# solarSwitcherV2_0.net
KiCad netlist of a schematic drawn in EAGLE
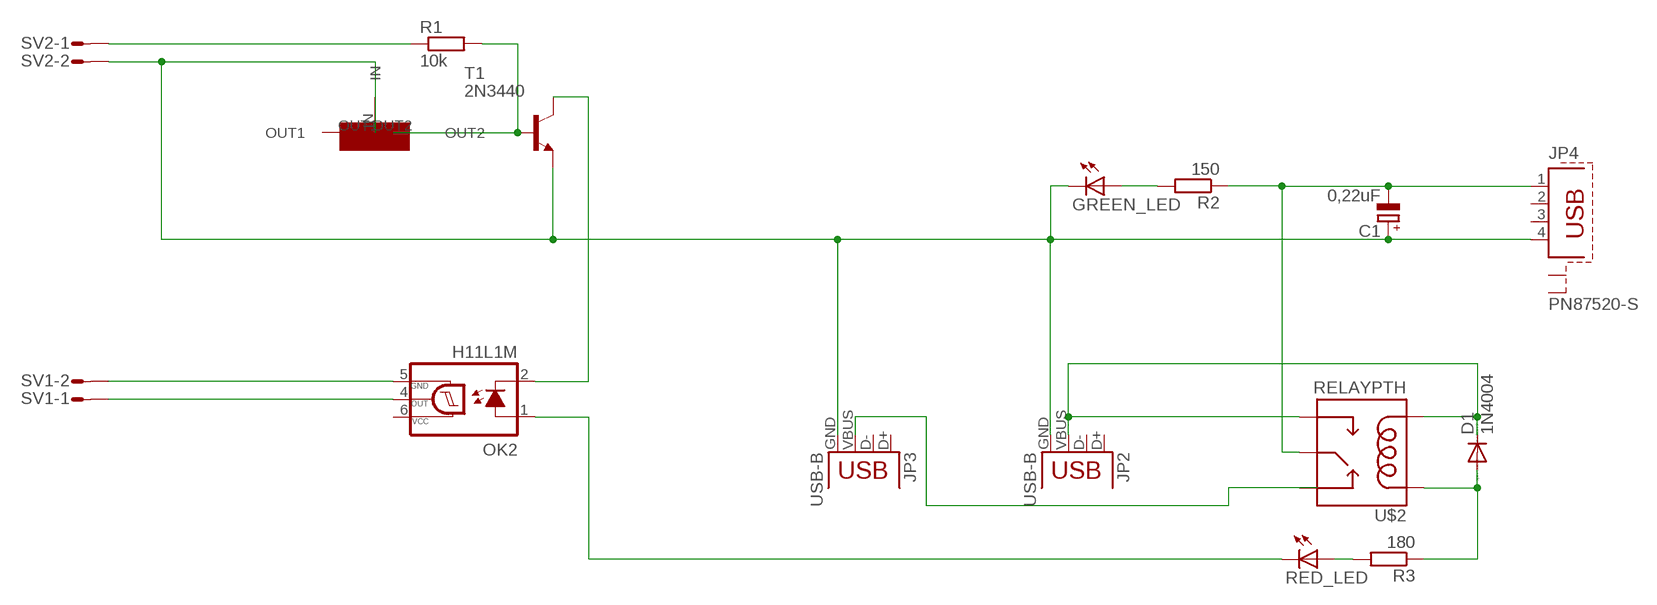
[diagram p0: schematic, sheet 1]

(export (version "E")
  (design (tool "Eeschema 10.0.6"))
  (components
    (comp (ref "C1")
      (value "0,22uF")
      (footprint "eagle-import:150CLZ-1014")
      (libsource (lib "eagle-import") (part "CPOL-EU150CLZ-1014"))
    )
    (comp (ref "D1")
      (value "1N4004")
      (footprint "eagle-import:DO41-10")
      (libsource (lib "eagle-import") (part "1N4004"))
    )
    (comp (ref "GREEN_LED")
      (value "LED5MM")
      (footprint "eagle-import:LED5MM")
      (libsource (lib "eagle-import") (part "LED5MM"))
    )
    (comp (ref "JP2")
      (value "USB-B")
      (footprint "eagle-import:USB-B-PTH")
      (libsource (lib "eagle-import") (part "USBPTH"))
    )
    (comp (ref "JP3")
      (value "USB-B")
      (footprint "eagle-import:USB-B-PTH")
      (libsource (lib "eagle-import") (part "USBPTH"))
    )
    (comp (ref "JP4")
      (value "PN87520-S")
      (footprint "eagle-import:PN87520-S")
      (libsource (lib "eagle-import") (part "PN87520-S"))
    )
    (comp (ref "OK2")
      (value "H11L1M")
      (footprint "eagle-import:DIL06")
      (fields (field (name "MF") "FAIRCHILD SEMICONDUCTOR") (field (name "MPN") "H11L1-M"))
      (libsource (lib "eagle-import") (part "H11LM1"))
    )
    (comp (ref "R1")
      (value "10k")
      (footprint "eagle-import:0207_10")
      (libsource (lib "eagle-import") (part "R-EU_0207/10"))
    )
    (comp (ref "R2")
      (value "150")
      (footprint "eagle-import:0207_10")
      (libsource (lib "eagle-import") (part "R-EU_0207/10"))
    )
    (comp (ref "R3")
      (value "180")
      (footprint "eagle-import:0207_10")
      (libsource (lib "eagle-import") (part "R-EU_0207/10"))
    )
    (comp (ref "RED_LED")
      (value "LED5MM")
      (footprint "eagle-import:LED5MM")
      (libsource (lib "eagle-import") (part "LED5MM"))
    )
    (comp (ref "SV1")
      (value "L02P")
      (footprint "eagle-import:L02P")
      (libsource (lib "eagle-import") (part "L02P"))
    )
    (comp (ref "SV2")
      (value "L02P")
      (footprint "eagle-import:L02P")
      (libsource (lib "eagle-import") (part "L02P"))
    )
    (comp (ref "T1")
      (value "2N3440")
      (footprint "eagle-import:TO5")
      (libsource (lib "eagle-import") (part "2N3440"))
    )
    (comp (ref "U$2")
      (value "RELAYPTH")
      (footprint "eagle-import:SRD-05VDC-SL-C")
      (libsource (lib "eagle-import") (part "RELAYPTH"))
    )
    (comp (ref "U$5")
      (value "20k")
      (footprint "eagle-import:POT_TRIMMER")
      (libsource (lib "eagle-import") (part "POT_TRIMMER"))
    )
  )
  (nets
    (net (code "1") (name "/VCC") (class "Default")
      (node (ref "OK2") (pin "6") (pinfunction "VCC_6") (pintype "power_in"))
    )
    (net (code "2") (name "Net-(C1-Pad-)") (class "Default")
      (node (ref "C1") (pin "-") (pinfunction "-_-") (pintype "passive"))
      (node (ref "JP4") (pin "1") (pinfunction "1_1") (pintype "passive"))
      (node (ref "R2") (pin "1") (pinfunction "1_1") (pintype "passive"))
      (node (ref "U$2") (pin "SWCOMMON") (pinfunction "SWCOMMON_SWCOMMON") (pintype "bidirectional"))
    )
    (net (code "3") (name "Net-(D1-PadA)") (class "Default")
      (node (ref "D1") (pin "A") (pinfunction "A_A") (pintype "passive"))
      (node (ref "R3") (pin "1") (pinfunction "1_1") (pintype "passive"))
      (node (ref "U$2") (pin "COIL1") (pinfunction "COIL1_COIL1") (pintype "bidirectional"))
    )
    (net (code "4") (name "Net-(D1-PadC)") (class "Default")
      (node (ref "D1") (pin "C") (pinfunction "C_C") (pintype "passive"))
      (node (ref "JP2") (pin "VBUS") (pinfunction "VBUS_VBUS") (pintype "bidirectional"))
      (node (ref "U$2") (pin "COIL0") (pinfunction "COIL0_COIL0") (pintype "bidirectional"))
      (node (ref "U$2") (pin "SWOPEN") (pinfunction "SWOPEN_SWOPEN") (pintype "bidirectional"))
    )
    (net (code "5") (name "Net-(GREEN_LED-C)") (class "Default")
      (node (ref "C1") (pin "+") (pinfunction "+_+") (pintype "passive"))
      (node (ref "GREEN_LED") (pin "K") (pinfunction "C_K") (pintype "passive"))
      (node (ref "JP2") (pin "GND") (pinfunction "GND_GND") (pintype "bidirectional"))
      (node (ref "JP3") (pin "GND") (pinfunction "GND_GND") (pintype "bidirectional"))
      (node (ref "JP4") (pin "4") (pinfunction "4_4") (pintype "passive"))
      (node (ref "SV2") (pin "2") (pinfunction "S_2") (pintype "passive"))
      (node (ref "T1") (pin "1") (pinfunction "E_1") (pintype "passive"))
      (node (ref "U$5") (pin "IN") (pinfunction "IN_IN") (pintype "bidirectional"))
    )
    (net (code "6") (name "Net-(GREEN_LED-PadA)") (class "Default")
      (node (ref "GREEN_LED") (pin "A") (pinfunction "A_A") (pintype "passive"))
      (node (ref "R2") (pin "2") (pinfunction "2_2") (pintype "passive"))
    )
    (net (code "7") (name "Net-(OK2-A)") (class "Default")
      (node (ref "OK2") (pin "1") (pinfunction "A_1") (pintype "passive"))
      (node (ref "RED_LED") (pin "K") (pinfunction "C_K") (pintype "passive"))
    )
    (net (code "8") (name "Net-(OK2-C)") (class "Default")
      (node (ref "OK2") (pin "2") (pinfunction "C_2") (pintype "passive"))
      (node (ref "T1") (pin "3") (pinfunction "C_3") (pintype "passive"))
    )
    (net (code "9") (name "Net-(OK2-GND)") (class "Default")
      (node (ref "OK2") (pin "5") (pinfunction "GND_5") (pintype "power_in"))
      (node (ref "SV1") (pin "2") (pinfunction "S_2") (pintype "passive"))
    )
    (net (code "10") (name "Net-(OK2-OUT)") (class "Default")
      (node (ref "OK2") (pin "4") (pinfunction "OUT_4") (pintype "output"))
      (node (ref "SV1") (pin "1") (pinfunction "S_1") (pintype "passive"))
    )
    (net (code "11") (name "Net-(R3-Pad2)") (class "Default")
      (node (ref "R3") (pin "2") (pinfunction "2_2") (pintype "passive"))
      (node (ref "RED_LED") (pin "A") (pinfunction "A_A") (pintype "passive"))
    )
    (net (code "12") (name "Net-(SV2A-S)") (class "Default")
      (node (ref "R1") (pin "1") (pinfunction "1_1") (pintype "passive"))
      (node (ref "SV2") (pin "1") (pinfunction "S_1") (pintype "passive"))
    )
    (net (code "13") (name "Net-(T1-B)") (class "Default")
      (node (ref "R1") (pin "2") (pinfunction "2_2") (pintype "passive"))
      (node (ref "T1") (pin "2") (pinfunction "B_2") (pintype "passive"))
      (node (ref "U$5") (pin "OUT2") (pinfunction "OUT2_OUT2") (pintype "bidirectional"))
    )
    (net (code "14") (name "Net-(U$2-SWCLOSE)") (class "Default")
      (node (ref "JP3") (pin "VBUS") (pinfunction "VBUS_VBUS") (pintype "bidirectional"))
      (node (ref "U$2") (pin "SWCLOSED") (pinfunction "SWCLOSE_SWCLOSED") (pintype "bidirectional"))
    )
    (net (code "15") (name "unconnected-(JP2-PadD+)") (class "Default")
      (node (ref "JP2") (pin "D+") (pinfunction "D+_D+") (pintype "bidirectional"))
    )
    (net (code "16") (name "unconnected-(JP2-PadD-)") (class "Default")
      (node (ref "JP2") (pin "D-") (pinfunction "D-_D-") (pintype "bidirectional"))
    )
    (net (code "17") (name "unconnected-(JP3-PadD+)") (class "Default")
      (node (ref "JP3") (pin "D+") (pinfunction "D+_D+") (pintype "bidirectional"))
    )
    (net (code "18") (name "unconnected-(JP3-PadD-)") (class "Default")
      (node (ref "JP3") (pin "D-") (pinfunction "D-_D-") (pintype "bidirectional"))
    )
    (net (code "19") (name "unconnected-(JP4-Pad2)") (class "Default")
      (node (ref "JP4") (pin "2") (pinfunction "2_2") (pintype "passive"))
    )
    (net (code "20") (name "unconnected-(JP4-Pad3)") (class "Default")
      (node (ref "JP4") (pin "3") (pinfunction "3_3") (pintype "passive"))
    )
    (net (code "21") (name "unconnected-(JP4-PadS1)") (class "Default")
      (node (ref "JP4") (pin "S1") (pinfunction "S1_S1") (pintype "passive"))
    )
    (net (code "22") (name "unconnected-(JP4-PadS2)") (class "Default")
      (node (ref "JP4") (pin "S2") (pinfunction "S2_S2") (pintype "passive"))
    )
    (net (code "23") (name "unconnected-(U$5-PadOUT1)") (class "Default")
      (node (ref "U$5") (pin "OUT1") (pinfunction "OUT1_OUT1") (pintype "bidirectional"))
    )
  )
)
